# TCA.net
KiCad netlist of a schematic drawn in Altium Designer
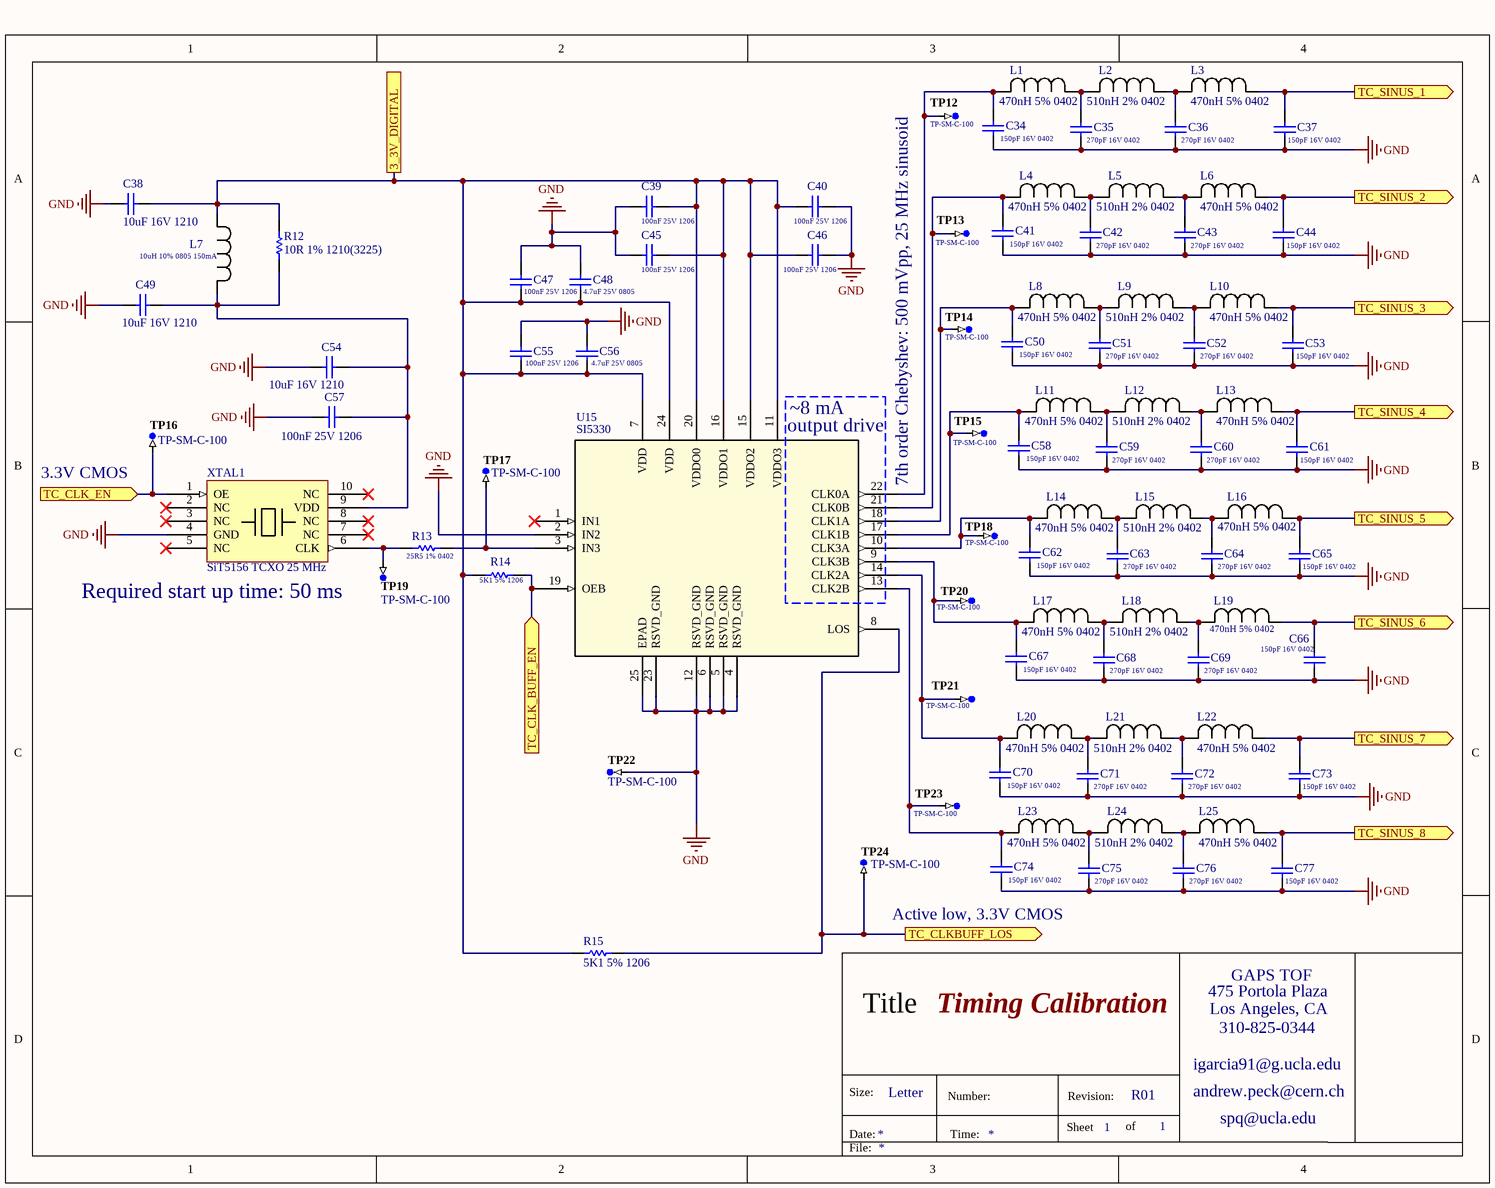
[diagram p0: TCA.SchDoc]

(export (version "E")
  (design (tool "Eeschema 10.0.6"))
  (components
    (comp (ref "C34")
      (value "150pF 16V 0402")
      (footprint "CAPC0402(1005)60_N")
      (description "CAP 150pF 16V ±10% 0402 (1005 Metric) Thickness 0.6mm SMD")
      (fields (field (name "TOLERANCE") "Â±10%"))
      (libsource (lib "Altium Content Vault") (part "CAP"))
    )
    (comp (ref "C35")
      (value "270pF 16V 0402")
      (footprint "CAPC0402(1005)60_N")
      (description "CAP 270pF 16V ±10% 0402 (1005 Metric) Thickness 0.6mm SMD")
      (fields (field (name "TOLERANCE") "Â±10%"))
      (libsource (lib "Altium Content Vault") (part "CAP"))
    )
    (comp (ref "C36")
      (value "270pF 16V 0402")
      (footprint "CAPC0402(1005)60_N")
      (description "CAP 270pF 16V ±10% 0402 (1005 Metric) Thickness 0.6mm SMD")
      (fields (field (name "TOLERANCE") "Â±10%"))
      (libsource (lib "Altium Content Vault") (part "CAP"))
    )
    (comp (ref "C37")
      (value "150pF 16V 0402")
      (footprint "CAPC0402(1005)60_N")
      (description "CAP 150pF 16V ±10% 0402 (1005 Metric) Thickness 0.6mm SMD")
      (fields (field (name "TOLERANCE") "Â±10%"))
      (libsource (lib "Altium Content Vault") (part "CAP"))
    )
    (comp (ref "C38")
      (value "10uF 16V 1210")
      (footprint "CAPC1210(3225)280_L")
      (description "CAP 10uF 16V ±10% 1210 (3225 Metric) Thickness 2.8mm SMD")
      (fields (field (name "TOLERANCE") "Â±10%"))
      (libsource (lib "Altium Content Vault") (part "CAP"))
    )
    (comp (ref "C39")
      (value "100nF 25V 1206")
      (footprint "CAPC1206(3216)170_M")
      (description "CAP 100nF 25V ±10% 1206 (3216 Metric) Thickness 1.7mm SMD")
      (fields (field (name "TOLERANCE") "Â±10%"))
      (libsource (lib "Altium Content Vault") (part "CAP"))
    )
    (comp (ref "C40")
      (value "100nF 25V 1206")
      (footprint "CAPC1206(3216)170_M")
      (description "CAP 100nF 25V ±10% 1206 (3216 Metric) Thickness 1.7mm SMD")
      (fields (field (name "TOLERANCE") "Â±10%"))
      (libsource (lib "Altium Content Vault") (part "CAP"))
    )
    (comp (ref "C41")
      (value "150pF 16V 0402")
      (footprint "CAPC0402(1005)60_N")
      (description "CAP 150pF 16V ±10% 0402 (1005 Metric) Thickness 0.6mm SMD")
      (fields (field (name "TOLERANCE") "Â±10%"))
      (libsource (lib "Altium Content Vault") (part "CAP"))
    )
    (comp (ref "C42")
      (value "270pF 16V 0402")
      (footprint "CAPC0402(1005)60_N")
      (description "CAP 270pF 16V ±10% 0402 (1005 Metric) Thickness 0.6mm SMD")
      (fields (field (name "TOLERANCE") "Â±10%"))
      (libsource (lib "Altium Content Vault") (part "CAP"))
    )
    (comp (ref "C43")
      (value "270pF 16V 0402")
      (footprint "CAPC0402(1005)60_N")
      (description "CAP 270pF 16V ±10% 0402 (1005 Metric) Thickness 0.6mm SMD")
      (fields (field (name "TOLERANCE") "Â±10%"))
      (libsource (lib "Altium Content Vault") (part "CAP"))
    )
    (comp (ref "C44")
      (value "150pF 16V 0402")
      (footprint "CAPC0402(1005)60_N")
      (description "CAP 150pF 16V ±10% 0402 (1005 Metric) Thickness 0.6mm SMD")
      (fields (field (name "TOLERANCE") "Â±10%"))
      (libsource (lib "Altium Content Vault") (part "CAP"))
    )
    (comp (ref "C45")
      (value "100nF 25V 1206")
      (footprint "CAPC1206(3216)170_M")
      (description "CAP 100nF 25V ±10% 1206 (3216 Metric) Thickness 1.7mm SMD")
      (fields (field (name "TOLERANCE") "Â±10%"))
      (libsource (lib "Altium Content Vault") (part "CAP"))
    )
    (comp (ref "C46")
      (value "100nF 25V 1206")
      (footprint "CAPC1206(3216)170_M")
      (description "CAP 100nF 25V ±10% 1206 (3216 Metric) Thickness 1.7mm SMD")
      (fields (field (name "TOLERANCE") "Â±10%"))
      (libsource (lib "Altium Content Vault") (part "CAP"))
    )
    (comp (ref "C47")
      (value "100nF 25V 1206")
      (footprint "CAPC1206(3216)170_M")
      (description "CAP 100nF 25V ±10% 1206 (3216 Metric) Thickness 1.7mm SMD")
      (fields (field (name "TOLERANCE") "Â±10%"))
      (libsource (lib "Altium Content Vault") (part "CAP"))
    )
    (comp (ref "C48")
      (value "4.7uF 25V 0805")
      (footprint "CAPC0805(2012)145_L")
      (description "CAP 4.7uF 25V ±10% 0805 (2012 Metric) Thickness 1.45mm SMD")
      (fields (field (name "TOLERANCE") "Â±10%"))
      (libsource (lib "Altium Content Vault") (part "CAP"))
    )
    (comp (ref "C49")
      (value "10uF 16V 1210")
      (footprint "CAPC1210(3225)280_L")
      (description "CAP 10uF 16V ±10% 1210 (3225 Metric) Thickness 2.8mm SMD")
      (fields (field (name "TOLERANCE") "Â±10%"))
      (libsource (lib "Altium Content Vault") (part "CAP"))
    )
    (comp (ref "C50")
      (value "150pF 16V 0402")
      (footprint "CAPC0402(1005)60_N")
      (description "CAP 150pF 16V ±10% 0402 (1005 Metric) Thickness 0.6mm SMD")
      (fields (field (name "TOLERANCE") "Â±10%"))
      (libsource (lib "Altium Content Vault") (part "CAP"))
    )
    (comp (ref "C51")
      (value "270pF 16V 0402")
      (footprint "CAPC0402(1005)60_N")
      (description "CAP 270pF 16V ±10% 0402 (1005 Metric) Thickness 0.6mm SMD")
      (fields (field (name "TOLERANCE") "Â±10%"))
      (libsource (lib "Altium Content Vault") (part "CAP"))
    )
    (comp (ref "C52")
      (value "270pF 16V 0402")
      (footprint "CAPC0402(1005)60_N")
      (description "CAP 270pF 16V ±10% 0402 (1005 Metric) Thickness 0.6mm SMD")
      (fields (field (name "TOLERANCE") "Â±10%"))
      (libsource (lib "Altium Content Vault") (part "CAP"))
    )
    (comp (ref "C53")
      (value "150pF 16V 0402")
      (footprint "CAPC0402(1005)60_N")
      (description "CAP 150pF 16V ±10% 0402 (1005 Metric) Thickness 0.6mm SMD")
      (fields (field (name "TOLERANCE") "Â±10%"))
      (libsource (lib "Altium Content Vault") (part "CAP"))
    )
    (comp (ref "C54")
      (value "10uF 16V 1210")
      (footprint "CAPC1210(3225)280_L")
      (description "CAP 10uF 16V ±10% 1210 (3225 Metric) Thickness 2.8mm SMD")
      (fields (field (name "TOLERANCE") "Â±10%"))
      (libsource (lib "Altium Content Vault") (part "CAP"))
    )
    (comp (ref "C55")
      (value "100nF 25V 1206")
      (footprint "CAPC1206(3216)170_M")
      (description "CAP 100nF 25V ±10% 1206 (3216 Metric) Thickness 1.7mm SMD")
      (fields (field (name "TOLERANCE") "Â±10%"))
      (libsource (lib "Altium Content Vault") (part "CAP"))
    )
    (comp (ref "C56")
      (value "4.7uF 25V 0805")
      (footprint "CAPC0805(2012)145_L")
      (description "CAP 4.7uF 25V ±10% 0805 (2012 Metric) Thickness 1.45mm SMD")
      (fields (field (name "TOLERANCE") "Â±10%"))
      (libsource (lib "Altium Content Vault") (part "CAP"))
    )
    (comp (ref "C57")
      (value "100nF 25V 1206")
      (footprint "CAPC1206(3216)170_M")
      (description "CAP 100nF 25V ±10% 1206 (3216 Metric) Thickness 1.7mm SMD")
      (fields (field (name "TOLERANCE") "Â±10%"))
      (libsource (lib "Altium Content Vault") (part "CAP"))
    )
    (comp (ref "C58")
      (value "150pF 16V 0402")
      (footprint "CAPC0402(1005)60_N")
      (description "CAP 150pF 16V ±10% 0402 (1005 Metric) Thickness 0.6mm SMD")
      (fields (field (name "TOLERANCE") "Â±10%"))
      (libsource (lib "Altium Content Vault") (part "CAP"))
    )
    (comp (ref "C59")
      (value "270pF 16V 0402")
      (footprint "CAPC0402(1005)60_N")
      (description "CAP 270pF 16V ±10% 0402 (1005 Metric) Thickness 0.6mm SMD")
      (fields (field (name "TOLERANCE") "Â±10%"))
      (libsource (lib "Altium Content Vault") (part "CAP"))
    )
    (comp (ref "C60")
      (value "270pF 16V 0402")
      (footprint "CAPC0402(1005)60_N")
      (description "CAP 270pF 16V ±10% 0402 (1005 Metric) Thickness 0.6mm SMD")
      (fields (field (name "TOLERANCE") "Â±10%"))
      (libsource (lib "Altium Content Vault") (part "CAP"))
    )
    (comp (ref "C61")
      (value "150pF 16V 0402")
      (footprint "CAPC0402(1005)60_N")
      (description "CAP 150pF 16V ±10% 0402 (1005 Metric) Thickness 0.6mm SMD")
      (fields (field (name "TOLERANCE") "Â±10%"))
      (libsource (lib "Altium Content Vault") (part "CAP"))
    )
    (comp (ref "C62")
      (value "150pF 16V 0402")
      (footprint "CAPC0402(1005)60_N")
      (description "CAP 150pF 16V ±10% 0402 (1005 Metric) Thickness 0.6mm SMD")
      (fields (field (name "TOLERANCE") "Â±10%"))
      (libsource (lib "Altium Content Vault") (part "CAP"))
    )
    (comp (ref "C63")
      (value "270pF 16V 0402")
      (footprint "CAPC0402(1005)60_N")
      (description "CAP 270pF 16V ±10% 0402 (1005 Metric) Thickness 0.6mm SMD")
      (fields (field (name "TOLERANCE") "Â±10%"))
      (libsource (lib "Altium Content Vault") (part "CAP"))
    )
    (comp (ref "C64")
      (value "270pF 16V 0402")
      (footprint "CAPC0402(1005)60_N")
      (description "CAP 270pF 16V ±10% 0402 (1005 Metric) Thickness 0.6mm SMD")
      (fields (field (name "TOLERANCE") "Â±10%"))
      (libsource (lib "Altium Content Vault") (part "CAP"))
    )
    (comp (ref "C65")
      (value "150pF 16V 0402")
      (footprint "CAPC0402(1005)60_N")
      (description "CAP 150pF 16V ±10% 0402 (1005 Metric) Thickness 0.6mm SMD")
      (fields (field (name "TOLERANCE") "Â±10%"))
      (libsource (lib "Altium Content Vault") (part "CAP"))
    )
    (comp (ref "C66")
      (value "150pF 16V 0402")
      (footprint "CAPC0402(1005)60_N")
      (description "CAP 150pF 16V ±10% 0402 (1005 Metric) Thickness 0.6mm SMD")
      (fields (field (name "TOLERANCE") "Â±10%"))
      (libsource (lib "Altium Content Vault") (part "CAP"))
    )
    (comp (ref "C67")
      (value "150pF 16V 0402")
      (footprint "CAPC0402(1005)60_N")
      (description "CAP 150pF 16V ±10% 0402 (1005 Metric) Thickness 0.6mm SMD")
      (fields (field (name "TOLERANCE") "Â±10%"))
      (libsource (lib "Altium Content Vault") (part "CAP"))
    )
    (comp (ref "C68")
      (value "270pF 16V 0402")
      (footprint "CAPC0402(1005)60_N")
      (description "CAP 270pF 16V ±10% 0402 (1005 Metric) Thickness 0.6mm SMD")
      (fields (field (name "TOLERANCE") "Â±10%"))
      (libsource (lib "Altium Content Vault") (part "CAP"))
    )
    (comp (ref "C69")
      (value "270pF 16V 0402")
      (footprint "CAPC0402(1005)60_N")
      (description "CAP 270pF 16V ±10% 0402 (1005 Metric) Thickness 0.6mm SMD")
      (fields (field (name "TOLERANCE") "Â±10%"))
      (libsource (lib "Altium Content Vault") (part "CAP"))
    )
    (comp (ref "C70")
      (value "150pF 16V 0402")
      (footprint "CAPC0402(1005)60_N")
      (description "CAP 150pF 16V ±10% 0402 (1005 Metric) Thickness 0.6mm SMD")
      (fields (field (name "TOLERANCE") "Â±10%"))
      (libsource (lib "Altium Content Vault") (part "CAP"))
    )
    (comp (ref "C71")
      (value "270pF 16V 0402")
      (footprint "CAPC0402(1005)60_N")
      (description "CAP 270pF 16V ±10% 0402 (1005 Metric) Thickness 0.6mm SMD")
      (fields (field (name "TOLERANCE") "Â±10%"))
      (libsource (lib "Altium Content Vault") (part "CAP"))
    )
    (comp (ref "C72")
      (value "270pF 16V 0402")
      (footprint "CAPC0402(1005)60_N")
      (description "CAP 270pF 16V ±10% 0402 (1005 Metric) Thickness 0.6mm SMD")
      (fields (field (name "TOLERANCE") "Â±10%"))
      (libsource (lib "Altium Content Vault") (part "CAP"))
    )
    (comp (ref "C73")
      (value "150pF 16V 0402")
      (footprint "CAPC0402(1005)60_N")
      (description "CAP 150pF 16V ±10% 0402 (1005 Metric) Thickness 0.6mm SMD")
      (fields (field (name "TOLERANCE") "Â±10%"))
      (libsource (lib "Altium Content Vault") (part "CAP"))
    )
    (comp (ref "C74")
      (value "150pF 16V 0402")
      (footprint "CAPC0402(1005)60_N")
      (description "CAP 150pF 16V ±10% 0402 (1005 Metric) Thickness 0.6mm SMD")
      (fields (field (name "TOLERANCE") "Â±10%"))
      (libsource (lib "Altium Content Vault") (part "CAP"))
    )
    (comp (ref "C75")
      (value "270pF 16V 0402")
      (footprint "CAPC0402(1005)60_N")
      (description "CAP 270pF 16V ±10% 0402 (1005 Metric) Thickness 0.6mm SMD")
      (fields (field (name "TOLERANCE") "Â±10%"))
      (libsource (lib "Altium Content Vault") (part "CAP"))
    )
    (comp (ref "C76")
      (value "270pF 16V 0402")
      (footprint "CAPC0402(1005)60_N")
      (description "CAP 270pF 16V ±10% 0402 (1005 Metric) Thickness 0.6mm SMD")
      (fields (field (name "TOLERANCE") "Â±10%"))
      (libsource (lib "Altium Content Vault") (part "CAP"))
    )
    (comp (ref "C77")
      (value "150pF 16V 0402")
      (footprint "CAPC0402(1005)60_N")
      (description "CAP 150pF 16V ±10% 0402 (1005 Metric) Thickness 0.6mm SMD")
      (fields (field (name "TOLERANCE") "Â±10%"))
      (libsource (lib "Altium Content Vault") (part "CAP"))
    )
    (comp (ref "L1")
      (value "470nH 5% 0402")
      (footprint "IND_1005")
      (description "Fixed Inductors 470nH 5% 0.12 A 1.5 Ohms")
      (fields (field (name "MANUFACTURER_PART_NUMBER") "MLF1005VR47JT000"))
      (libsource (lib "MLF1005VR47JT000") (part "MLF1005VR47JT000"))
    )
    (comp (ref "L2")
      (value "510nH 2% 0402")
      (footprint "IND_1005")
      (description "Fixed Inductors 0402 510nH 2% 70mA 10.2ohms")
      (fields (field (name "MANUFACTURER_PART_NUMBER") "MHQ1005P10NGTD25"))
      (libsource (lib "MHQ1005PR51GT000") (part "MHQ1005P10NGTD25"))
    )
    (comp (ref "L3")
      (value "470nH 5% 0402")
      (footprint "IND_1005")
      (description "Fixed Inductors 470nH 5% 0.12 A 1.5 Ohms")
      (fields (field (name "MANUFACTURER_PART_NUMBER") "MLF1005VR47JT000"))
      (libsource (lib "MLF1005VR47JT000") (part "MLF1005VR47JT000"))
    )
    (comp (ref "L4")
      (value "470nH 5% 0402")
      (footprint "IND_1005")
      (description "Fixed Inductors 470nH 5% 0.12 A 1.5 Ohms")
      (fields (field (name "MANUFACTURER_PART_NUMBER") "MLF1005VR47JT000"))
      (libsource (lib "MLF1005VR47JT000") (part "MLF1005VR47JT000"))
    )
    (comp (ref "L5")
      (value "510nH 2% 0402")
      (footprint "IND_1005")
      (description "Fixed Inductors 0402 510nH 2% 70mA 10.2ohms")
      (fields (field (name "MANUFACTURER_PART_NUMBER") "MHQ1005P10NGTD25"))
      (libsource (lib "MHQ1005PR51GT000") (part "MHQ1005P10NGTD25"))
    )
    (comp (ref "L6")
      (value "470nH 5% 0402")
      (footprint "IND_1005")
      (description "Fixed Inductors 470nH 5% 0.12 A 1.5 Ohms")
      (fields (field (name "MANUFACTURER_PART_NUMBER") "MLF1005VR47JT000"))
      (libsource (lib "MLF1005VR47JT000") (part "MLF1005VR47JT000"))
    )
    (comp (ref "L7")
      (value "10uH 10% 0805 150mA")
      (footprint "IND_TAIYO_LBR201")
      (description "Fixed Inductors 0805 10uH 468mOhms +/-10%Tol 150mA")
      (fields (field (name "MANUFACTURER_PART_NUMBER") "LBR2012T100K"))
      (libsource (lib "LBR2012T100K") (part "LBR2012T100K"))
    )
    (comp (ref "L8")
      (value "470nH 5% 0402")
      (footprint "IND_1005")
      (description "Fixed Inductors 470nH 5% 0.12 A 1.5 Ohms")
      (fields (field (name "MANUFACTURER_PART_NUMBER") "MLF1005VR47JT000"))
      (libsource (lib "MLF1005VR47JT000") (part "MLF1005VR47JT000"))
    )
    (comp (ref "L9")
      (value "510nH 2% 0402")
      (footprint "IND_1005")
      (description "Fixed Inductors 0402 510nH 2% 70mA 10.2ohms")
      (fields (field (name "MANUFACTURER_PART_NUMBER") "MHQ1005P10NGTD25"))
      (libsource (lib "MHQ1005PR51GT000") (part "MHQ1005P10NGTD25"))
    )
    (comp (ref "L10")
      (value "470nH 5% 0402")
      (footprint "IND_1005")
      (description "Fixed Inductors 470nH 5% 0.12 A 1.5 Ohms")
      (fields (field (name "MANUFACTURER_PART_NUMBER") "MLF1005VR47JT000"))
      (libsource (lib "MLF1005VR47JT000") (part "MLF1005VR47JT000"))
    )
    (comp (ref "L11")
      (value "470nH 5% 0402")
      (footprint "IND_1005")
      (description "Fixed Inductors 470nH 5% 0.12 A 1.5 Ohms")
      (fields (field (name "MANUFACTURER_PART_NUMBER") "MLF1005VR47JT000"))
      (libsource (lib "MLF1005VR47JT000") (part "MLF1005VR47JT000"))
    )
    (comp (ref "L12")
      (value "510nH 2% 0402")
      (footprint "IND_1005")
      (description "Fixed Inductors 0402 510nH 2% 70mA 10.2ohms")
      (fields (field (name "MANUFACTURER_PART_NUMBER") "MHQ1005P10NGTD25"))
      (libsource (lib "MHQ1005PR51GT000") (part "MHQ1005P10NGTD25"))
    )
    (comp (ref "L13")
      (value "470nH 5% 0402")
      (footprint "IND_1005")
      (description "Fixed Inductors 470nH 5% 0.12 A 1.5 Ohms")
      (fields (field (name "MANUFACTURER_PART_NUMBER") "MLF1005VR47JT000"))
      (libsource (lib "MLF1005VR47JT000") (part "MLF1005VR47JT000"))
    )
    (comp (ref "L14")
      (value "470nH 5% 0402")
      (footprint "IND_1005")
      (description "Fixed Inductors 470nH 5% 0.12 A 1.5 Ohms")
      (fields (field (name "MANUFACTURER_PART_NUMBER") "MLF1005VR47JT000"))
      (libsource (lib "MLF1005VR47JT000") (part "MLF1005VR47JT000"))
    )
    (comp (ref "L15")
      (value "510nH 2% 0402")
      (footprint "IND_1005")
      (description "Fixed Inductors 0402 510nH 2% 70mA 10.2ohms")
      (fields (field (name "MANUFACTURER_PART_NUMBER") "MHQ1005P10NGTD25"))
      (libsource (lib "MHQ1005PR51GT000") (part "MHQ1005P10NGTD25"))
    )
    (comp (ref "L16")
      (value "470nH 5% 0402")
      (footprint "IND_1005")
      (description "Fixed Inductors 470nH 5% 0.12 A 1.5 Ohms")
      (fields (field (name "MANUFACTURER_PART_NUMBER") "MLF1005VR47JT000"))
      (libsource (lib "MLF1005VR47JT000") (part "MLF1005VR47JT000"))
    )
    (comp (ref "L17")
      (value "470nH 5% 0402")
      (footprint "IND_1005")
      (description "Fixed Inductors 470nH 5% 0.12 A 1.5 Ohms")
      (fields (field (name "MANUFACTURER_PART_NUMBER") "MLF1005VR47JT000"))
      (libsource (lib "MLF1005VR47JT000") (part "MLF1005VR47JT000"))
    )
    (comp (ref "L18")
      (value "510nH 2% 0402")
      (footprint "IND_1005")
      (description "Fixed Inductors 0402 510nH 2% 70mA 10.2ohms")
      (fields (field (name "MANUFACTURER_PART_NUMBER") "MHQ1005P10NGTD25"))
      (libsource (lib "MHQ1005PR51GT000") (part "MHQ1005P10NGTD25"))
    )
    (comp (ref "L19")
      (value "470nH 5% 0402")
      (footprint "IND_1005")
      (description "Fixed Inductors 470nH 5% 0.12 A 1.5 Ohms")
      (fields (field (name "MANUFACTURER_PART_NUMBER") "MLF1005VR47JT000"))
      (libsource (lib "MLF1005VR47JT000") (part "MLF1005VR47JT000"))
    )
    (comp (ref "L20")
      (value "470nH 5% 0402")
      (footprint "IND_1005")
      (description "Fixed Inductors 470nH 5% 0.12 A 1.5 Ohms")
      (fields (field (name "MANUFACTURER_PART_NUMBER") "MLF1005VR47JT000"))
      (libsource (lib "MLF1005VR47JT000") (part "MLF1005VR47JT000"))
    )
    (comp (ref "L21")
      (value "510nH 2% 0402")
      (footprint "IND_1005")
      (description "Fixed Inductors 0402 510nH 2% 70mA 10.2ohms")
      (fields (field (name "MANUFACTURER_PART_NUMBER") "MHQ1005P10NGTD25"))
      (libsource (lib "MHQ1005PR51GT000") (part "MHQ1005P10NGTD25"))
    )
    (comp (ref "L22")
      (value "470nH 5% 0402")
      (footprint "IND_1005")
      (description "Fixed Inductors 470nH 5% 0.12 A 1.5 Ohms")
      (fields (field (name "MANUFACTURER_PART_NUMBER") "MLF1005VR47JT000"))
      (libsource (lib "MLF1005VR47JT000") (part "MLF1005VR47JT000"))
    )
    (comp (ref "L23")
      (value "470nH 5% 0402")
      (footprint "IND_1005")
      (description "Fixed Inductors 470nH 5% 0.12 A 1.5 Ohms")
      (fields (field (name "MANUFACTURER_PART_NUMBER") "MLF1005VR47JT000"))
      (libsource (lib "MLF1005VR47JT000") (part "MLF1005VR47JT000"))
    )
    (comp (ref "L24")
      (value "510nH 2% 0402")
      (footprint "IND_1005")
      (description "Fixed Inductors 0402 510nH 2% 70mA 10.2ohms")
      (fields (field (name "MANUFACTURER_PART_NUMBER") "MHQ1005P10NGTD25"))
      (libsource (lib "MHQ1005PR51GT000") (part "MHQ1005P10NGTD25"))
    )
    (comp (ref "L25")
      (value "470nH 5% 0402")
      (footprint "IND_1005")
      (description "Fixed Inductors 470nH 5% 0.12 A 1.5 Ohms")
      (fields (field (name "MANUFACTURER_PART_NUMBER") "MLF1005VR47JT000"))
      (libsource (lib "MLF1005VR47JT000") (part "MLF1005VR47JT000"))
    )
    (comp (ref "R12")
      (value "10R 1% 1210(3225)")
      (footprint "RESC1210(3225)_N")
      (description "10R 0.5W 1% 1210 (3225 Metric)  SMD")
      (fields (field (name "POWER") "0.5 W") (field (name "TOLERANCE") "1 %"))
      (libsource (lib "Altium Content Vault") (part "RES"))
    )
    (comp (ref "R13")
      (value "25R5 1% 0402")
      (footprint "RESC0402(1005)_M")
      (description "25R5 0.063W 1% 0402 (1005 Metric)  SMD")
      (fields (field (name "TOLERANCE") "1 %") (field (name "POWER") "0.063 W"))
      (libsource (lib "Altium Content Vault") (part "RES"))
    )
    (comp (ref "R14")
      (value "5K1 5% 1206")
      (footprint "RESC1206(3216)_N")
      (description "5K1 0.25W 5% 1206 (3216 Metric)  SMD")
      (fields (field (name "POWER") "0.25 W") (field (name "TOLERANCE") "5 %"))
      (libsource (lib "Altium Content Vault") (part "RES"))
    )
    (comp (ref "R15")
      (value "5K1 5% 1206")
      (footprint "RESC1206(3216)_N")
      (description "5K1 0.25W 5% 1206 (3216 Metric)  SMD")
      (fields (field (name "POWER") "0.25 W") (field (name "TOLERANCE") "5 %"))
      (libsource (lib "Altium Content Vault") (part "RES"))
    )
    (comp (ref "TP12")
      (value "TP-SM-C-100")
      (footprint "TP-SM-C-100")
      (description "Test Point, Surface Mount, Circular, Pad Diameter 1 mm")
      (fields (field (name "MANUFACTURER") "No Vendor"))
      (libsource (lib "Altium Content Vault") (part "TP-SM"))
    )
    (comp (ref "TP13")
      (value "TP-SM-C-100")
      (footprint "TP-SM-C-100")
      (description "Test Point, Surface Mount, Circular, Pad Diameter 1 mm")
      (fields (field (name "MANUFACTURER") "No Vendor"))
      (libsource (lib "Altium Content Vault") (part "TP-SM"))
    )
    (comp (ref "TP14")
      (value "TP-SM-C-100")
      (footprint "TP-SM-C-100")
      (description "Test Point, Surface Mount, Circular, Pad Diameter 1 mm")
      (fields (field (name "MANUFACTURER") "No Vendor"))
      (libsource (lib "Altium Content Vault") (part "TP-SM"))
    )
    (comp (ref "TP15")
      (value "TP-SM-C-100")
      (footprint "TP-SM-C-100")
      (description "Test Point, Surface Mount, Circular, Pad Diameter 1 mm")
      (fields (field (name "MANUFACTURER") "No Vendor"))
      (libsource (lib "Altium Content Vault") (part "TP-SM"))
    )
    (comp (ref "TP16")
      (value "TP-SM-C-100")
      (footprint "TP-SM-C-100")
      (description "Test Point, Surface Mount, Circular, Pad Diameter 1 mm")
      (fields (field (name "MANUFACTURER") "No Vendor"))
      (libsource (lib "Altium Content Vault") (part "TP-SM"))
    )
    (comp (ref "TP17")
      (value "TP-SM-C-100")
      (footprint "TP-SM-C-100")
      (description "Test Point, Surface Mount, Circular, Pad Diameter 1 mm")
      (fields (field (name "MANUFACTURER") "No Vendor"))
      (libsource (lib "Altium Content Vault") (part "TP-SM"))
    )
    (comp (ref "TP18")
      (value "TP-SM-C-100")
      (footprint "TP-SM-C-100")
      (description "Test Point, Surface Mount, Circular, Pad Diameter 1 mm")
      (fields (field (name "MANUFACTURER") "No Vendor"))
      (libsource (lib "Altium Content Vault") (part "TP-SM"))
    )
    (comp (ref "TP19")
      (value "TP-SM-C-100")
      (footprint "TP-SM-C-100")
      (description "Test Point, Surface Mount, Circular, Pad Diameter 1 mm")
      (fields (field (name "MANUFACTURER") "No Vendor"))
      (libsource (lib "Altium Content Vault") (part "TP-SM"))
    )
    (comp (ref "TP20")
      (value "TP-SM-C-100")
      (footprint "TP-SM-C-100")
      (description "Test Point, Surface Mount, Circular, Pad Diameter 1 mm")
      (fields (field (name "MANUFACTURER") "No Vendor"))
      (libsource (lib "Altium Content Vault") (part "TP-SM"))
    )
    (comp (ref "TP21")
      (value "TP-SM-C-100")
      (footprint "TP-SM-C-100")
      (description "Test Point, Surface Mount, Circular, Pad Diameter 1 mm")
      (fields (field (name "MANUFACTURER") "No Vendor"))
      (libsource (lib "Altium Content Vault") (part "TP-SM"))
    )
    (comp (ref "TP22")
      (value "TP-SM-C-100")
      (footprint "TP-SM-C-100")
      (description "Test Point, Surface Mount, Circular, Pad Diameter 1 mm")
      (fields (field (name "MANUFACTURER") "No Vendor"))
      (libsource (lib "Altium Content Vault") (part "TP-SM"))
    )
    (comp (ref "TP23")
      (value "TP-SM-C-100")
      (footprint "TP-SM-C-100")
      (description "Test Point, Surface Mount, Circular, Pad Diameter 1 mm")
      (fields (field (name "MANUFACTURER") "No Vendor"))
      (libsource (lib "Altium Content Vault") (part "TP-SM"))
    )
    (comp (ref "TP24")
      (value "TP-SM-C-100")
      (footprint "TP-SM-C-100")
      (description "Test Point, Surface Mount, Circular, Pad Diameter 1 mm")
      (fields (field (name "MANUFACTURER") "No Vendor"))
      (libsource (lib "Altium Content Vault") (part "TP-SM"))
    )
    (comp (ref "U15")
      (value "SI5330")
      (footprint "QFN_24")
      (description "Imported")
      (fields (field (name "MANUFACTURER_PART_NUMBER") "si5330"))
      (libsource (lib "SI5330G-B00219-GM") (part "SI5330"))
    )
    (comp (ref "XTAL1")
      (value "SiT5156 TCXO 25 MHz")
      (description "Crystal oscillator")
      (libsource (lib "SIT5156AI-FK-33E0-25.000000X") (part "SiT5156"))
    )
  )
  (nets
    (net (code "1") (name "/3_3V_DIGITAL") (class "Default")
      (node (ref "C38") (pin "2") (pinfunction "2_2") (pintype "passive"))
      (node (ref "C39") (pin "1") (pinfunction "1_1") (pintype "passive"))
      (node (ref "C40") (pin "2") (pinfunction "2_2") (pintype "passive"))
      (node (ref "C45") (pin "1") (pinfunction "1_1") (pintype "passive"))
      (node (ref "C46") (pin "2") (pinfunction "2_2") (pintype "passive"))
      (node (ref "C47") (pin "1") (pinfunction "1_1") (pintype "passive"))
      (node (ref "C48") (pin "2") (pinfunction "2_2") (pintype "passive"))
      (node (ref "C55") (pin "1") (pinfunction "1_1") (pintype "passive"))
      (node (ref "C56") (pin "2") (pinfunction "2_2") (pintype "passive"))
      (node (ref "L7") (pin "2") (pinfunction "2_2") (pintype "passive"))
      (node (ref "R12") (pin "1") (pinfunction "1_1") (pintype "passive"))
      (node (ref "R14") (pin "2") (pinfunction "2_2") (pintype "passive"))
      (node (ref "R15") (pin "2") (pinfunction "2_2") (pintype "passive"))
      (node (ref "U15") (pin "11") (pinfunction "VDDO3_11") (pintype "power_in"))
      (node (ref "U15") (pin "15") (pinfunction "VDDO2_15") (pintype "power_in"))
      (node (ref "U15") (pin "16") (pinfunction "VDDO1_16") (pintype "power_in"))
      (node (ref "U15") (pin "20") (pinfunction "VDDO0_20") (pintype "power_in"))
      (node (ref "U15") (pin "24") (pinfunction "VDD_24") (pintype "power_in"))
      (node (ref "U15") (pin "7") (pinfunction "VDD_7") (pintype "power_in"))
    )
    (net (code "2") (name "/TC_CLKBUFF_LOS") (class "Default")
      (node (ref "R15") (pin "1") (pinfunction "1_1") (pintype "passive"))
      (node (ref "TP24") (pin "1") (pinfunction "1_1") (pintype "input"))
      (node (ref "U15") (pin "8") (pinfunction "LOS_8") (pintype "output"))
    )
    (net (code "3") (name "/TC_CLK_BUFF_EN") (class "Default")
      (node (ref "R14") (pin "1") (pinfunction "1_1") (pintype "passive"))
      (node (ref "U15") (pin "19") (pinfunction "OEB_19") (pintype "input"))
    )
    (net (code "4") (name "/TC_CLK_EN") (class "Default")
      (node (ref "TP16") (pin "1") (pinfunction "1_1") (pintype "input"))
      (node (ref "XTAL1") (pin "1") (pinfunction "OE_1") (pintype "input"))
    )
    (net (code "5") (name "/TC_SINUS_1") (class "Default")
      (node (ref "C37") (pin "2") (pinfunction "2_2") (pintype "passive"))
      (node (ref "L3") (pin "1") (pinfunction "1_1") (pintype "passive"))
    )
    (net (code "6") (name "/TC_SINUS_2") (class "Default")
      (node (ref "C44") (pin "2") (pinfunction "2_2") (pintype "passive"))
      (node (ref "L6") (pin "1") (pinfunction "1_1") (pintype "passive"))
    )
    (net (code "7") (name "/TC_SINUS_3") (class "Default")
      (node (ref "C53") (pin "2") (pinfunction "2_2") (pintype "passive"))
      (node (ref "L10") (pin "1") (pinfunction "1_1") (pintype "passive"))
    )
    (net (code "8") (name "/TC_SINUS_4") (class "Default")
      (node (ref "C61") (pin "2") (pinfunction "2_2") (pintype "passive"))
      (node (ref "L13") (pin "1") (pinfunction "1_1") (pintype "passive"))
    )
    (net (code "9") (name "/TC_SINUS_5") (class "Default")
      (node (ref "C65") (pin "2") (pinfunction "2_2") (pintype "passive"))
      (node (ref "L16") (pin "1") (pinfunction "1_1") (pintype "passive"))
    )
    (net (code "10") (name "/TC_SINUS_6") (class "Default")
      (node (ref "C66") (pin "2") (pinfunction "2_2") (pintype "passive"))
      (node (ref "L19") (pin "1") (pinfunction "1_1") (pintype "passive"))
    )
    (net (code "11") (name "/TC_SINUS_7") (class "Default")
      (node (ref "C73") (pin "2") (pinfunction "2_2") (pintype "passive"))
      (node (ref "L22") (pin "1") (pinfunction "1_1") (pintype "passive"))
    )
    (net (code "12") (name "/TC_SINUS_8") (class "Default")
      (node (ref "C77") (pin "2") (pinfunction "2_2") (pintype "passive"))
      (node (ref "L25") (pin "1") (pinfunction "1_1") (pintype "passive"))
    )
    (net (code "13") (name "GND") (class "Default")
      (node (ref "C34") (pin "1") (pinfunction "1_1") (pintype "passive"))
      (node (ref "C35") (pin "1") (pinfunction "1_1") (pintype "passive"))
      (node (ref "C36") (pin "1") (pinfunction "1_1") (pintype "passive"))
      (node (ref "C37") (pin "1") (pinfunction "1_1") (pintype "passive"))
      (node (ref "C38") (pin "1") (pinfunction "1_1") (pintype "passive"))
      (node (ref "C39") (pin "2") (pinfunction "2_2") (pintype "passive"))
      (node (ref "C40") (pin "1") (pinfunction "1_1") (pintype "passive"))
      (node (ref "C41") (pin "1") (pinfunction "1_1") (pintype "passive"))
      (node (ref "C42") (pin "1") (pinfunction "1_1") (pintype "passive"))
      (node (ref "C43") (pin "1") (pinfunction "1_1") (pintype "passive"))
      (node (ref "C44") (pin "1") (pinfunction "1_1") (pintype "passive"))
      (node (ref "C45") (pin "2") (pinfunction "2_2") (pintype "passive"))
      (node (ref "C46") (pin "1") (pinfunction "1_1") (pintype "passive"))
      (node (ref "C47") (pin "2") (pinfunction "2_2") (pintype "passive"))
      (node (ref "C48") (pin "1") (pinfunction "1_1") (pintype "passive"))
      (node (ref "C49") (pin "1") (pinfunction "1_1") (pintype "passive"))
      (node (ref "C50") (pin "1") (pinfunction "1_1") (pintype "passive"))
      (node (ref "C51") (pin "1") (pinfunction "1_1") (pintype "passive"))
      (node (ref "C52") (pin "1") (pinfunction "1_1") (pintype "passive"))
      (node (ref "C53") (pin "1") (pinfunction "1_1") (pintype "passive"))
      (node (ref "C54") (pin "2") (pinfunction "2_2") (pintype "passive"))
      (node (ref "C55") (pin "2") (pinfunction "2_2") (pintype "passive"))
      (node (ref "C56") (pin "1") (pinfunction "1_1") (pintype "passive"))
      (node (ref "C57") (pin "2") (pinfunction "2_2") (pintype "passive"))
      (node (ref "C58") (pin "1") (pinfunction "1_1") (pintype "passive"))
      (node (ref "C59") (pin "1") (pinfunction "1_1") (pintype "passive"))
      (node (ref "C60") (pin "1") (pinfunction "1_1") (pintype "passive"))
      (node (ref "C61") (pin "1") (pinfunction "1_1") (pintype "passive"))
      (node (ref "C62") (pin "1") (pinfunction "1_1") (pintype "passive"))
      (node (ref "C63") (pin "1") (pinfunction "1_1") (pintype "passive"))
      (node (ref "C64") (pin "1") (pinfunction "1_1") (pintype "passive"))
      (node (ref "C65") (pin "1") (pinfunction "1_1") (pintype "passive"))
      (node (ref "C66") (pin "1") (pinfunction "1_1") (pintype "passive"))
      (node (ref "C67") (pin "1") (pinfunction "1_1") (pintype "passive"))
      (node (ref "C68") (pin "1") (pinfunction "1_1") (pintype "passive"))
      (node (ref "C69") (pin "1") (pinfunction "1_1") (pintype "passive"))
      (node (ref "C70") (pin "1") (pinfunction "1_1") (pintype "passive"))
      (node (ref "C71") (pin "1") (pinfunction "1_1") (pintype "passive"))
      (node (ref "C72") (pin "1") (pinfunction "1_1") (pintype "passive"))
      (node (ref "C73") (pin "1") (pinfunction "1_1") (pintype "passive"))
      (node (ref "C74") (pin "1") (pinfunction "1_1") (pintype "passive"))
      (node (ref "C75") (pin "1") (pinfunction "1_1") (pintype "passive"))
      (node (ref "C76") (pin "1") (pinfunction "1_1") (pintype "passive"))
      (node (ref "C77") (pin "1") (pinfunction "1_1") (pintype "passive"))
      (node (ref "TP22") (pin "1") (pinfunction "1_1") (pintype "input"))
      (node (ref "U15") (pin "12") (pinfunction "RSVD_GND_12") (pintype "power_in"))
      (node (ref "U15") (pin "2") (pinfunction "IN2_2") (pintype "input"))
      (node (ref "U15") (pin "23") (pinfunction "RSVD_GND_23") (pintype "power_in"))
      (node (ref "U15") (pin "25") (pinfunction "EPAD_25") (pintype "passive"))
      (node (ref "U15") (pin "4") (pinfunction "RSVD_GND_4") (pintype "power_in"))
      (node (ref "U15") (pin "5") (pinfunction "RSVD_GND_5") (pintype "power_in"))
      (node (ref "U15") (pin "6") (pinfunction "RSVD_GND_6") (pintype "power_in"))
      (node (ref "XTAL1") (pin "4") (pinfunction "GND_4") (pintype "passive"))
    )
    (net (code "14") (name "Net-(C35-Pad2)") (class "Default")
      (node (ref "C35") (pin "2") (pinfunction "2_2") (pintype "passive"))
      (node (ref "L1") (pin "1") (pinfunction "1_1") (pintype "passive"))
      (node (ref "L2") (pin "2") (pinfunction "2_2") (pintype "passive"))
    )
    (net (code "15") (name "Net-(C36-Pad2)") (class "Default")
      (node (ref "C36") (pin "2") (pinfunction "2_2") (pintype "passive"))
      (node (ref "L2") (pin "1") (pinfunction "1_1") (pintype "passive"))
      (node (ref "L3") (pin "2") (pinfunction "2_2") (pintype "passive"))
    )
    (net (code "16") (name "Net-(C42-Pad2)") (class "Default")
      (node (ref "C42") (pin "2") (pinfunction "2_2") (pintype "passive"))
      (node (ref "L4") (pin "1") (pinfunction "1_1") (pintype "passive"))
      (node (ref "L5") (pin "2") (pinfunction "2_2") (pintype "passive"))
    )
    (net (code "17") (name "Net-(C43-Pad2)") (class "Default")
      (node (ref "C43") (pin "2") (pinfunction "2_2") (pintype "passive"))
      (node (ref "L5") (pin "1") (pinfunction "1_1") (pintype "passive"))
      (node (ref "L6") (pin "2") (pinfunction "2_2") (pintype "passive"))
    )
    (net (code "18") (name "Net-(C51-Pad2)") (class "Default")
      (node (ref "C51") (pin "2") (pinfunction "2_2") (pintype "passive"))
      (node (ref "L8") (pin "1") (pinfunction "1_1") (pintype "passive"))
      (node (ref "L9") (pin "2") (pinfunction "2_2") (pintype "passive"))
    )
    (net (code "19") (name "Net-(C52-Pad2)") (class "Default")
      (node (ref "C52") (pin "2") (pinfunction "2_2") (pintype "passive"))
      (node (ref "L10") (pin "2") (pinfunction "2_2") (pintype "passive"))
      (node (ref "L9") (pin "1") (pinfunction "1_1") (pintype "passive"))
    )
    (net (code "20") (name "Net-(C59-Pad2)") (class "Default")
      (node (ref "C59") (pin "2") (pinfunction "2_2") (pintype "passive"))
      (node (ref "L11") (pin "1") (pinfunction "1_1") (pintype "passive"))
      (node (ref "L12") (pin "2") (pinfunction "2_2") (pintype "passive"))
    )
    (net (code "21") (name "Net-(C60-Pad2)") (class "Default")
      (node (ref "C60") (pin "2") (pinfunction "2_2") (pintype "passive"))
      (node (ref "L12") (pin "1") (pinfunction "1_1") (pintype "passive"))
      (node (ref "L13") (pin "2") (pinfunction "2_2") (pintype "passive"))
    )
    (net (code "22") (name "Net-(C63-Pad2)") (class "Default")
      (node (ref "C63") (pin "2") (pinfunction "2_2") (pintype "passive"))
      (node (ref "L14") (pin "1") (pinfunction "1_1") (pintype "passive"))
      (node (ref "L15") (pin "2") (pinfunction "2_2") (pintype "passive"))
    )
    (net (code "23") (name "Net-(C64-Pad2)") (class "Default")
      (node (ref "C64") (pin "2") (pinfunction "2_2") (pintype "passive"))
      (node (ref "L15") (pin "1") (pinfunction "1_1") (pintype "passive"))
      (node (ref "L16") (pin "2") (pinfunction "2_2") (pintype "passive"))
    )
    (net (code "24") (name "Net-(C68-Pad2)") (class "Default")
      (node (ref "C68") (pin "2") (pinfunction "2_2") (pintype "passive"))
      (node (ref "L17") (pin "1") (pinfunction "1_1") (pintype "passive"))
      (node (ref "L18") (pin "2") (pinfunction "2_2") (pintype "passive"))
    )
    (net (code "25") (name "Net-(C69-Pad2)") (class "Default")
      (node (ref "C69") (pin "2") (pinfunction "2_2") (pintype "passive"))
      (node (ref "L18") (pin "1") (pinfunction "1_1") (pintype "passive"))
      (node (ref "L19") (pin "2") (pinfunction "2_2") (pintype "passive"))
    )
    (net (code "26") (name "Net-(C71-Pad2)") (class "Default")
      (node (ref "C71") (pin "2") (pinfunction "2_2") (pintype "passive"))
      (node (ref "L20") (pin "1") (pinfunction "1_1") (pintype "passive"))
      (node (ref "L21") (pin "2") (pinfunction "2_2") (pintype "passive"))
    )
    (net (code "27") (name "Net-(C72-Pad2)") (class "Default")
      (node (ref "C72") (pin "2") (pinfunction "2_2") (pintype "passive"))
      (node (ref "L21") (pin "1") (pinfunction "1_1") (pintype "passive"))
      (node (ref "L22") (pin "2") (pinfunction "2_2") (pintype "passive"))
    )
    (net (code "28") (name "Net-(C75-Pad2)") (class "Default")
      (node (ref "C75") (pin "2") (pinfunction "2_2") (pintype "passive"))
      (node (ref "L23") (pin "1") (pinfunction "1_1") (pintype "passive"))
      (node (ref "L24") (pin "2") (pinfunction "2_2") (pintype "passive"))
    )
    (net (code "29") (name "Net-(C76-Pad2)") (class "Default")
      (node (ref "C76") (pin "2") (pinfunction "2_2") (pintype "passive"))
      (node (ref "L24") (pin "1") (pinfunction "1_1") (pintype "passive"))
      (node (ref "L25") (pin "2") (pinfunction "2_2") (pintype "passive"))
    )
    (net (code "30") (name "Net-(U15-CLK0A)") (class "Default")
      (node (ref "C34") (pin "2") (pinfunction "2_2") (pintype "passive"))
      (node (ref "L1") (pin "2") (pinfunction "2_2") (pintype "passive"))
      (node (ref "TP12") (pin "1") (pinfunction "1_1") (pintype "input"))
      (node (ref "U15") (pin "22") (pinfunction "CLK0A_22") (pintype "output"))
    )
    (net (code "31") (name "Net-(U15-CLK0B)") (class "Default")
      (node (ref "C41") (pin "2") (pinfunction "2_2") (pintype "passive"))
      (node (ref "L4") (pin "2") (pinfunction "2_2") (pintype "passive"))
      (node (ref "TP13") (pin "1") (pinfunction "1_1") (pintype "input"))
      (node (ref "U15") (pin "21") (pinfunction "CLK0B_21") (pintype "output"))
    )
    (net (code "32") (name "Net-(U15-CLK1A)") (class "Default")
      (node (ref "C50") (pin "2") (pinfunction "2_2") (pintype "passive"))
      (node (ref "L8") (pin "2") (pinfunction "2_2") (pintype "passive"))
      (node (ref "TP14") (pin "1") (pinfunction "1_1") (pintype "input"))
      (node (ref "U15") (pin "18") (pinfunction "CLK1A_18") (pintype "output"))
    )
    (net (code "33") (name "Net-(U15-CLK1B)") (class "Default")
      (node (ref "C58") (pin "2") (pinfunction "2_2") (pintype "passive"))
      (node (ref "L11") (pin "2") (pinfunction "2_2") (pintype "passive"))
      (node (ref "TP15") (pin "1") (pinfunction "1_1") (pintype "input"))
      (node (ref "U15") (pin "17") (pinfunction "CLK1B_17") (pintype "output"))
    )
    (net (code "34") (name "Net-(U15-CLK2A)") (class "Default")
      (node (ref "C70") (pin "2") (pinfunction "2_2") (pintype "passive"))
      (node (ref "L20") (pin "2") (pinfunction "2_2") (pintype "passive"))
      (node (ref "TP21") (pin "1") (pinfunction "1_1") (pintype "input"))
      (node (ref "U15") (pin "14") (pinfunction "CLK2A_14") (pintype "output"))
    )
    (net (code "35") (name "Net-(U15-CLK2B)") (class "Default")
      (node (ref "C74") (pin "2") (pinfunction "2_2") (pintype "passive"))
      (node (ref "L23") (pin "2") (pinfunction "2_2") (pintype "passive"))
      (node (ref "TP23") (pin "1") (pinfunction "1_1") (pintype "input"))
      (node (ref "U15") (pin "13") (pinfunction "CLK2B_13") (pintype "output"))
    )
    (net (code "36") (name "Net-(U15-CLK3A)") (class "Default")
      (node (ref "C62") (pin "2") (pinfunction "2_2") (pintype "passive"))
      (node (ref "L14") (pin "2") (pinfunction "2_2") (pintype "passive"))
      (node (ref "TP18") (pin "1") (pinfunction "1_1") (pintype "input"))
      (node (ref "U15") (pin "10") (pinfunction "CLK3A_10") (pintype "output"))
    )
    (net (code "37") (name "Net-(U15-CLK3B)") (class "Default")
      (node (ref "C67") (pin "2") (pinfunction "2_2") (pintype "passive"))
      (node (ref "L17") (pin "2") (pinfunction "2_2") (pintype "passive"))
      (node (ref "TP20") (pin "1") (pinfunction "1_1") (pintype "input"))
      (node (ref "U15") (pin "9") (pinfunction "CLK3B_9") (pintype "output"))
    )
    (net (code "38") (name "Net-(U15-IN3)") (class "Default")
      (node (ref "R13") (pin "2") (pinfunction "2_2") (pintype "passive"))
      (node (ref "TP17") (pin "1") (pinfunction "1_1") (pintype "input"))
      (node (ref "U15") (pin "3") (pinfunction "IN3_3") (pintype "input"))
    )
    (net (code "39") (name "Net-(XTAL1-CLK)") (class "Default")
      (node (ref "R13") (pin "1") (pinfunction "1_1") (pintype "passive"))
      (node (ref "TP19") (pin "1") (pinfunction "1_1") (pintype "input"))
      (node (ref "XTAL1") (pin "6") (pinfunction "CLK_6") (pintype "output"))
    )
    (net (code "40") (name "Net-(XTAL1-VDD)") (class "Default")
      (node (ref "C49") (pin "2") (pinfunction "2_2") (pintype "passive"))
      (node (ref "C54") (pin "1") (pinfunction "1_1") (pintype "passive"))
      (node (ref "C57") (pin "1") (pinfunction "1_1") (pintype "passive"))
      (node (ref "L7") (pin "1") (pinfunction "1_1") (pintype "passive"))
      (node (ref "R12") (pin "2") (pinfunction "2_2") (pintype "passive"))
      (node (ref "XTAL1") (pin "9") (pinfunction "VDD_9") (pintype "power_in"))
    )
    (net (code "41") (name "unconnected-(U15-IN1-Pad1)") (class "Default")
      (node (ref "U15") (pin "1") (pinfunction "IN1_1") (pintype "input+no_connect"))
    )
    (net (code "42") (name "unconnected-(XTAL1-NC-Pad2)") (class "Default")
      (node (ref "XTAL1") (pin "2") (pinfunction "NC_2") (pintype "passive+no_connect"))
    )
    (net (code "43") (name "unconnected-(XTAL1-NC-Pad3)") (class "Default")
      (node (ref "XTAL1") (pin "3") (pinfunction "NC_3") (pintype "passive+no_connect"))
    )
    (net (code "44") (name "unconnected-(XTAL1-NC-Pad5)") (class "Default")
      (node (ref "XTAL1") (pin "5") (pinfunction "NC_5") (pintype "passive+no_connect"))
    )
    (net (code "45") (name "unconnected-(XTAL1-NC-Pad7)") (class "Default")
      (node (ref "XTAL1") (pin "7") (pinfunction "NC_7") (pintype "passive+no_connect"))
    )
    (net (code "46") (name "unconnected-(XTAL1-NC-Pad8)") (class "Default")
      (node (ref "XTAL1") (pin "8") (pinfunction "NC_8") (pintype "passive+no_connect"))
    )
    (net (code "47") (name "unconnected-(XTAL1-NC-Pad10)") (class "Default")
      (node (ref "XTAL1") (pin "10") (pinfunction "NC_10") (pintype "passive+no_connect"))
    )
  )
)
